# BalEv_USB_v1_0.net
KiCad netlist of a schematic drawn in Altium Designer
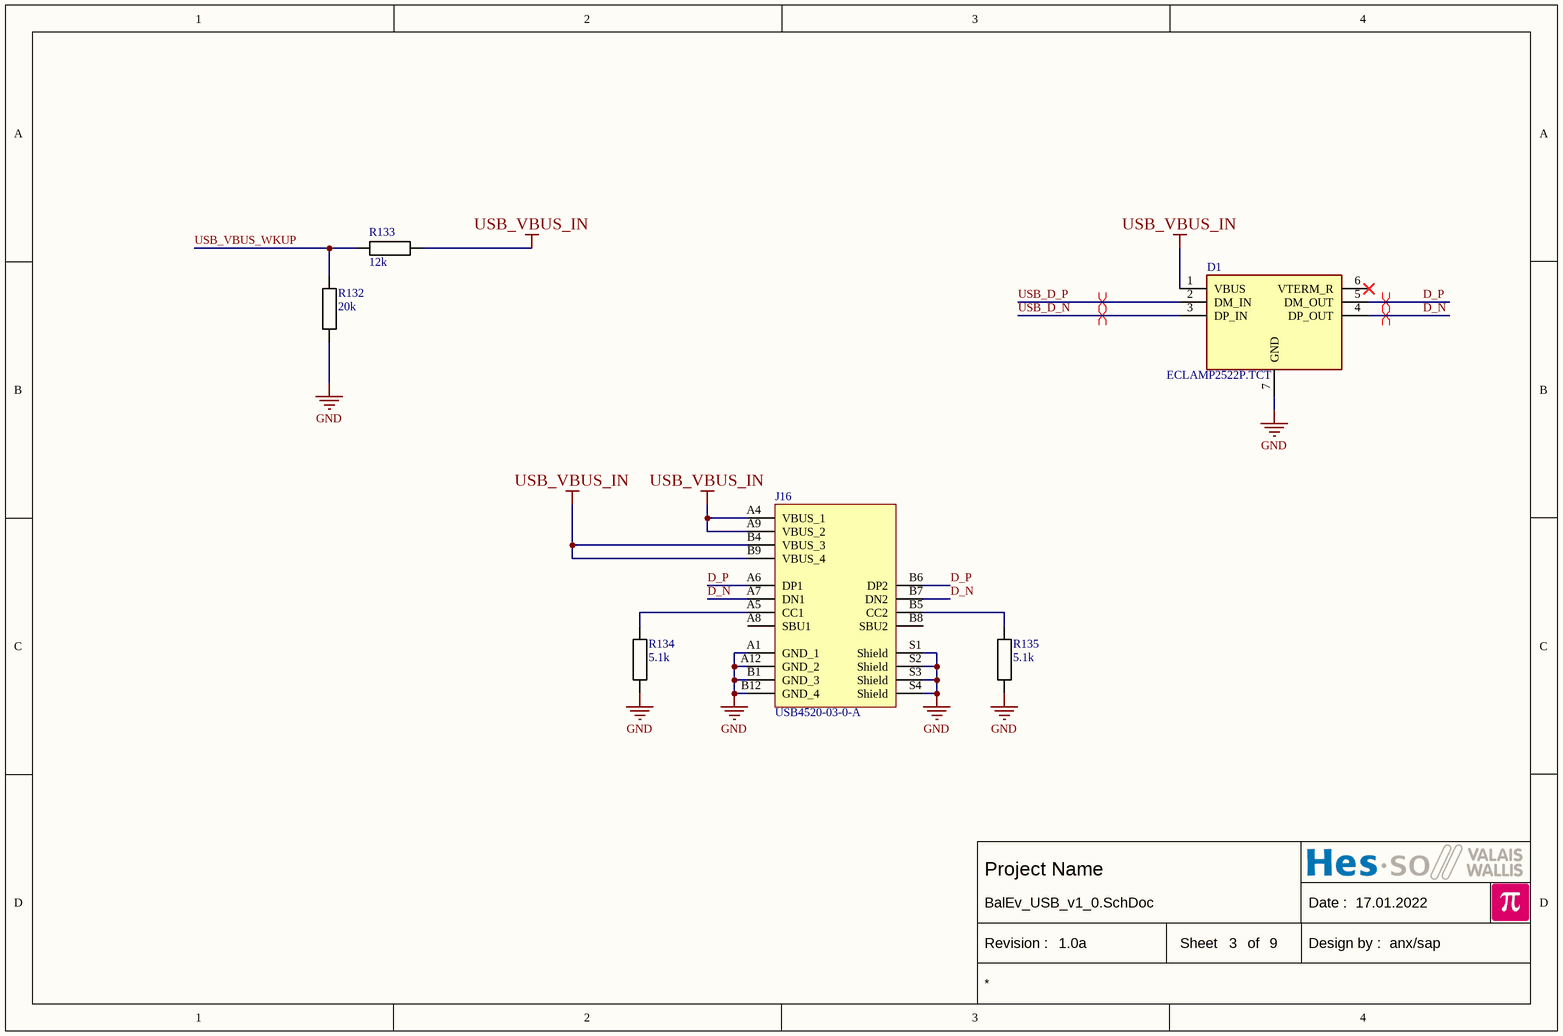
[diagram p0: BalEv_USB_v1_0.SchDoc]

(export (version "E")
  (design (tool "Eeschema 10.0.6"))
  (components
    (comp (ref "D1")
      (value "ECLAMP2522P.TCT")
      (footprint "SamacSys:SON50P160X160X65-7N")
      (description "Integrated Circuit")
      (libsource (lib "Diode") (part "ECLAMP2522P.___"))
    )
    (comp (ref "J16")
      (value "USB4520-03-0-A")
      (footprint "USB-C-SMD GCT USB4520030A")
      (description "Connector")
      (libsource (lib "Connector") (part "USB-C SMD GTC USB4520-03-0-A"))
    )
    (comp (ref "R132")
      (value "20k")
      (footprint "RESISTOR 1005 REFLOW")
      (description "Resistor")
      (libsource (lib "Resistor") (part "Resistor"))
    )
    (comp (ref "R133")
      (value "12k")
      (footprint "RESISTOR 1005 REFLOW")
      (description "Resistor")
      (libsource (lib "Resistor") (part "Resistor"))
    )
    (comp (ref "R134")
      (value "5.1k")
      (footprint "RESISTOR 1005 REFLOW")
      (description "Resistor")
      (libsource (lib "Resistor") (part "Resistor"))
    )
    (comp (ref "R135")
      (value "5.1k")
      (footprint "RESISTOR 1005 REFLOW")
      (description "Resistor")
      (libsource (lib "Resistor") (part "Resistor"))
    )
  )
  (nets
    (net (code "1") (name "/D_N") (class "Default")
      (node (ref "D1") (pin "4") (pinfunction "DP_OUT_4") (pintype "passive"))
      (node (ref "J16") (pin "A7") (pinfunction "DN1_A7") (pintype "passive"))
      (node (ref "J16") (pin "B7") (pinfunction "DN2_B7") (pintype "passive"))
    )
    (net (code "2") (name "/D_P") (class "Default")
      (node (ref "D1") (pin "5") (pinfunction "DM_OUT_5") (pintype "passive"))
      (node (ref "J16") (pin "A6") (pinfunction "DP1_A6") (pintype "passive"))
      (node (ref "J16") (pin "B6") (pinfunction "DP2_B6") (pintype "passive"))
    )
    (net (code "3") (name "/USB_D_N") (class "Default")
      (node (ref "D1") (pin "3") (pinfunction "DP_IN_3") (pintype "passive"))
    )
    (net (code "4") (name "/USB_D_P") (class "Default")
      (node (ref "D1") (pin "2") (pinfunction "DM_IN_2") (pintype "passive"))
    )
    (net (code "5") (name "/USB_VBUS_WKUP") (class "Default")
      (node (ref "R132") (pin "1") (pinfunction "1_1") (pintype "passive"))
      (node (ref "R133") (pin "2") (pinfunction "2_2") (pintype "passive"))
    )
    (net (code "6") (name "GND") (class "Default")
      (node (ref "D1") (pin "7") (pinfunction "GND_7") (pintype "passive"))
      (node (ref "J16") (pin "A1") (pinfunction "GND_1_A1") (pintype "passive"))
      (node (ref "J16") (pin "A12") (pinfunction "GND_2_A12") (pintype "passive"))
      (node (ref "J16") (pin "B1") (pinfunction "GND_3_B1") (pintype "passive"))
      (node (ref "J16") (pin "B12") (pinfunction "GND_4_B12") (pintype "passive"))
      (node (ref "J16") (pin "S1") (pinfunction "Shield_S1") (pintype "passive"))
      (node (ref "J16") (pin "S2") (pinfunction "Shield_S2") (pintype "passive"))
      (node (ref "J16") (pin "S3") (pinfunction "Shield_S3") (pintype "passive"))
      (node (ref "J16") (pin "S4") (pinfunction "Shield_S4") (pintype "passive"))
      (node (ref "R132") (pin "2") (pinfunction "2_2") (pintype "passive"))
      (node (ref "R134") (pin "2") (pinfunction "2_2") (pintype "passive"))
      (node (ref "R135") (pin "2") (pinfunction "2_2") (pintype "passive"))
    )
    (net (code "7") (name "Net-(J16-CC1)") (class "Default")
      (node (ref "J16") (pin "A5") (pinfunction "CC1_A5") (pintype "passive"))
      (node (ref "R134") (pin "1") (pinfunction "1_1") (pintype "passive"))
    )
    (net (code "8") (name "Net-(J16-CC2)") (class "Default")
      (node (ref "J16") (pin "B5") (pinfunction "CC2_B5") (pintype "passive"))
      (node (ref "R135") (pin "1") (pinfunction "1_1") (pintype "passive"))
    )
    (net (code "9") (name "USB_VBUS_IN") (class "Default")
      (node (ref "D1") (pin "1") (pinfunction "VBUS_1") (pintype "passive"))
      (node (ref "J16") (pin "A4") (pinfunction "VBUS_1_A4") (pintype "passive"))
      (node (ref "J16") (pin "A9") (pinfunction "VBUS_2_A9") (pintype "passive"))
      (node (ref "J16") (pin "B4") (pinfunction "VBUS_3_B4") (pintype "passive"))
      (node (ref "J16") (pin "B9") (pinfunction "VBUS_4_B9") (pintype "passive"))
      (node (ref "R133") (pin "1") (pinfunction "1_1") (pintype "passive"))
    )
    (net (code "10") (name "unconnected-(D1-VTERM_R-Pad6)") (class "Default")
      (node (ref "D1") (pin "6") (pinfunction "VTERM_R_6") (pintype "passive+no_connect"))
    )
    (net (code "11") (name "unconnected-(J16-SBU1-PadA8)") (class "Default")
      (node (ref "J16") (pin "A8") (pinfunction "SBU1_A8") (pintype "passive"))
    )
    (net (code "12") (name "unconnected-(J16-SBU2-PadB8)") (class "Default")
      (node (ref "J16") (pin "B8") (pinfunction "SBU2_B8") (pintype "passive"))
    )
  )
)
